# FE1_1S-SCH.net
KiCad netlist of a schematic drawn in Altium Designer
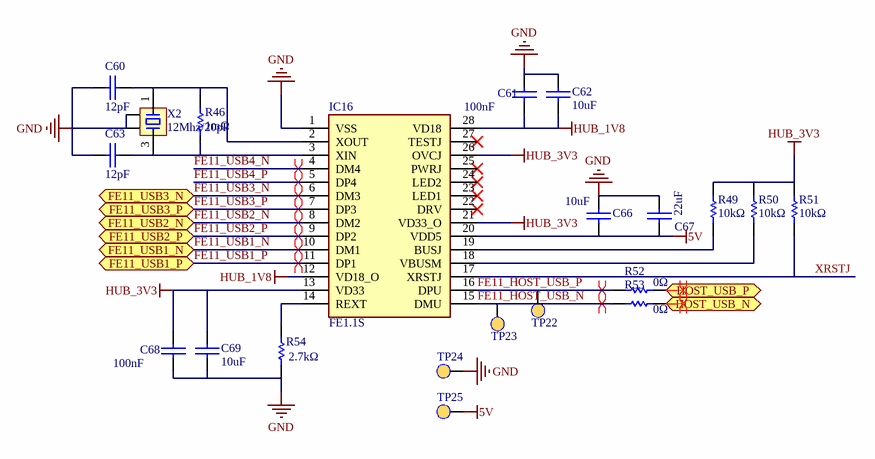
[diagram p0: FE1.1S-SCH.SchDoc]

(export (version "E")
  (design (tool "Eeschema 10.0.6"))
  (components
    (comp (ref "C60")
      (value "12pF")
      (footprint "C_0402")
      (description "贴片电容")
      (fields (field (name "MANUFACTURER_PART_NUMBER") "±5% /25V"))
      (libsource (lib "IntLib-Passive") (part "Cap_Chip"))
    )
    (comp (ref "C61")
      (value "100nF")
      (footprint "C_0402")
      (description "贴片电容")
      (fields (field (name "MANUFACTURER_PART_NUMBER") "±10% /25V"))
      (libsource (lib "IntLib-Passive") (part "Cap_Chip"))
    )
    (comp (ref "C62")
      (value "10uF")
      (footprint "C_0603")
      (description "贴片电容")
      (fields (field (name "MANUFACTURER_PART_NUMBER") "±10% /25V"))
      (libsource (lib "IntLib-Passive") (part "Cap_Chip"))
    )
    (comp (ref "C63")
      (value "12pF")
      (footprint "C_0402")
      (description "贴片电容")
      (fields (field (name "MANUFACTURER_PART_NUMBER") "±5% /25V"))
      (libsource (lib "IntLib-Passive") (part "Cap_Chip"))
    )
    (comp (ref "C66")
      (value "10uF")
      (footprint "C_0603")
      (description "贴片电容")
      (fields (field (name "MANUFACTURER_PART_NUMBER") "±10% /25V"))
      (libsource (lib "IntLib-Passive") (part "Cap_Chip"))
    )
    (comp (ref "C67")
      (value "22uF")
      (footprint "C_0805")
      (description "贴片电容")
      (fields (field (name "MANUFACTURER_PART_NUMBER") "±10% /25V"))
      (libsource (lib "IntLib-Passive") (part "Cap_Chip"))
    )
    (comp (ref "C68")
      (value "100nF")
      (footprint "C_0402")
      (description "贴片电容")
      (fields (field (name "MANUFACTURER_PART_NUMBER") "±10% /25V"))
      (libsource (lib "IntLib-Passive") (part "Cap_Chip"))
    )
    (comp (ref "C69")
      (value "10uF")
      (footprint "C_0603")
      (description "贴片电容")
      (fields (field (name "MANUFACTURER_PART_NUMBER") "±10% /25V"))
      (libsource (lib "IntLib-Passive") (part "Cap_Chip"))
    )
    (comp (ref "IC16")
      (value "FE1.1S")
      (footprint "SSOP-28N-150MIL")
      (description "USB2.0 Hub 4口芯片")
      (fields (field (name "MANUFACTURER_PART_NUMBER") "FE1.1S-BSOP28BCN"))
      (libsource (lib "IntLib-IC") (part "FE1.1S"))
    )
    (comp (ref "R46")
      (value "1mΩ")
      (footprint "R_0402")
      (description "贴片电阻")
      (fields (field (name "MANUFACTURER_PART_NUMBER") "±1%"))
      (libsource (lib "IntLib-Passive") (part "Res_Chip"))
    )
    (comp (ref "R49")
      (value "10kΩ")
      (footprint "R_0402")
      (description "贴片电阻")
      (fields (field (name "MANUFACTURER_PART_NUMBER") "±1%"))
      (libsource (lib "IntLib-Passive") (part "Res_Chip"))
    )
    (comp (ref "R50")
      (value "10kΩ")
      (footprint "R_0402")
      (description "贴片电阻")
      (fields (field (name "MANUFACTURER_PART_NUMBER") "±1%"))
      (libsource (lib "IntLib-Passive") (part "Res_Chip"))
    )
    (comp (ref "R51")
      (value "10kΩ")
      (footprint "R_0402")
      (description "贴片电阻")
      (fields (field (name "MANUFACTURER_PART_NUMBER") "±1%"))
      (libsource (lib "IntLib-Passive") (part "Res_Chip"))
    )
    (comp (ref "R52")
      (value "0Ω")
      (footprint "R_0603")
      (description "贴片电阻")
      (fields (field (name "MANUFACTURER_PART_NUMBER") "±1%"))
      (libsource (lib "IntLib-Passive") (part "Res_Chip"))
    )
    (comp (ref "R53")
      (value "0Ω")
      (footprint "R_0603")
      (description "贴片电阻")
      (fields (field (name "MANUFACTURER_PART_NUMBER") "±1%"))
      (libsource (lib "IntLib-Passive") (part "Res_Chip"))
    )
    (comp (ref "R54")
      (value "2.7kΩ")
      (footprint "R_0402")
      (description "贴片电阻")
      (fields (field (name "MANUFACTURER_PART_NUMBER") "±1%"))
      (libsource (lib "IntLib-Passive") (part "Res_Chip"))
    )
    (comp (ref "TP22")
      (value "TP")
      (footprint "TP1.4mm")
      (description "测试点")
      (libsource (lib "MiscParts") (part "TP"))
    )
    (comp (ref "TP23")
      (value "TP")
      (footprint "TP1.4mm")
      (description "测试点")
      (libsource (lib "MiscParts") (part "TP"))
    )
    (comp (ref "TP24")
      (value "TP")
      (footprint "TP1.4mm")
      (description "测试点")
      (libsource (lib "MiscParts") (part "TP"))
    )
    (comp (ref "TP25")
      (value "TP")
      (footprint "TP1.4mm")
      (description "测试点")
      (libsource (lib "MiscParts") (part "TP"))
    )
    (comp (ref "X2")
      (value "12Mhz/20pF")
      (footprint "XTAL_3225-4P")
      (description "4脚无源晶振")
      (libsource (lib "IntLib-Active") (part "Crystal_4P"))
    )
  )
  (nets
    (net (code "1") (name "/FE11_HOST_USB_N") (class "Default")
      (node (ref "IC16") (pin "15") (pinfunction "DMU_15") (pintype "passive"))
      (node (ref "R53") (pin "2") (pinfunction "2_2") (pintype "passive"))
      (node (ref "TP23") (pin "1") (pinfunction "TP_1") (pintype "passive"))
    )
    (net (code "2") (name "/FE11_HOST_USB_P") (class "Default")
      (node (ref "IC16") (pin "16") (pinfunction "DPU_16") (pintype "passive"))
      (node (ref "R52") (pin "2") (pinfunction "2_2") (pintype "passive"))
      (node (ref "TP22") (pin "1") (pinfunction "TP_1") (pintype "passive"))
    )
    (net (code "3") (name "/FE11_USB1_N") (class "Default")
      (node (ref "IC16") (pin "10") (pinfunction "DM1_10") (pintype "passive"))
    )
    (net (code "4") (name "/FE11_USB1_P") (class "Default")
      (node (ref "IC16") (pin "11") (pinfunction "DP1_11") (pintype "passive"))
    )
    (net (code "5") (name "/FE11_USB2_N") (class "Default")
      (node (ref "IC16") (pin "8") (pinfunction "DM2_8") (pintype "passive"))
    )
    (net (code "6") (name "/FE11_USB2_P") (class "Default")
      (node (ref "IC16") (pin "9") (pinfunction "DP2_9") (pintype "passive"))
    )
    (net (code "7") (name "/FE11_USB3_N") (class "Default")
      (node (ref "IC16") (pin "6") (pinfunction "DM3_6") (pintype "passive"))
    )
    (net (code "8") (name "/FE11_USB3_P") (class "Default")
      (node (ref "IC16") (pin "7") (pinfunction "DP3_7") (pintype "passive"))
    )
    (net (code "9") (name "/FE11_USB4_N") (class "Default")
      (node (ref "IC16") (pin "4") (pinfunction "DM4_4") (pintype "passive"))
    )
    (net (code "10") (name "/FE11_USB4_P") (class "Default")
      (node (ref "IC16") (pin "5") (pinfunction "DP4_5") (pintype "passive"))
    )
    (net (code "11") (name "/HOST_USB_N") (class "Default")
      (node (ref "R53") (pin "1") (pinfunction "1_1") (pintype "passive"))
    )
    (net (code "12") (name "/HOST_USB_P") (class "Default")
      (node (ref "R52") (pin "1") (pinfunction "1_1") (pintype "passive"))
    )
    (net (code "13") (name "/XRSTJ") (class "Default")
      (node (ref "IC16") (pin "17") (pinfunction "XRSTJ_17") (pintype "passive"))
      (node (ref "R51") (pin "1") (pinfunction "1_1") (pintype "passive"))
    )
    (net (code "14") (name "5V") (class "Default")
      (node (ref "C66") (pin "2") (pinfunction "2_2") (pintype "passive"))
      (node (ref "C67") (pin "1") (pinfunction "1_1") (pintype "passive"))
      (node (ref "IC16") (pin "20") (pinfunction "VDD5_20") (pintype "passive"))
      (node (ref "TP25") (pin "1") (pinfunction "TP_1") (pintype "passive"))
    )
    (net (code "15") (name "GND") (class "Default")
      (node (ref "C60") (pin "2") (pinfunction "2_2") (pintype "passive"))
      (node (ref "C61") (pin "2") (pinfunction "2_2") (pintype "passive"))
      (node (ref "C62") (pin "1") (pinfunction "1_1") (pintype "passive"))
      (node (ref "C63") (pin "1") (pinfunction "1_1") (pintype "passive"))
      (node (ref "C66") (pin "1") (pinfunction "1_1") (pintype "passive"))
      (node (ref "C67") (pin "2") (pinfunction "2_2") (pintype "passive"))
      (node (ref "C68") (pin "1") (pinfunction "1_1") (pintype "passive"))
      (node (ref "C69") (pin "2") (pinfunction "2_2") (pintype "passive"))
      (node (ref "IC16") (pin "1") (pinfunction "VSS_1") (pintype "passive"))
      (node (ref "R54") (pin "1") (pinfunction "1_1") (pintype "passive"))
      (node (ref "TP24") (pin "1") (pinfunction "TP_1") (pintype "passive"))
      (node (ref "X2") (pin "2") (pinfunction "2_2") (pintype "passive"))
      (node (ref "X2") (pin "4") (pinfunction "4_4") (pintype "passive"))
    )
    (net (code "16") (name "HUB_1V8") (class "Default")
      (node (ref "C61") (pin "1") (pinfunction "1_1") (pintype "passive"))
      (node (ref "C62") (pin "2") (pinfunction "2_2") (pintype "passive"))
      (node (ref "IC16") (pin "12") (pinfunction "VD18_O_12") (pintype "passive"))
      (node (ref "IC16") (pin "28") (pinfunction "VD18_28") (pintype "passive"))
    )
    (net (code "17") (name "HUB_3V3") (class "Default")
      (node (ref "C68") (pin "2") (pinfunction "2_2") (pintype "passive"))
      (node (ref "C69") (pin "1") (pinfunction "1_1") (pintype "passive"))
      (node (ref "IC16") (pin "13") (pinfunction "VD33_13") (pintype "passive"))
      (node (ref "IC16") (pin "21") (pinfunction "VD33_O_21") (pintype "passive"))
      (node (ref "IC16") (pin "26") (pinfunction "OVCJ_26") (pintype "passive"))
      (node (ref "R49") (pin "2") (pinfunction "2_2") (pintype "passive"))
      (node (ref "R50") (pin "2") (pinfunction "2_2") (pintype "passive"))
      (node (ref "R51") (pin "2") (pinfunction "2_2") (pintype "passive"))
    )
    (net (code "18") (name "Net-(IC16-BUSJ)") (class "Default")
      (node (ref "IC16") (pin "19") (pinfunction "BUSJ_19") (pintype "passive"))
      (node (ref "R49") (pin "1") (pinfunction "1_1") (pintype "passive"))
    )
    (net (code "19") (name "Net-(IC16-REXT)") (class "Default")
      (node (ref "IC16") (pin "14") (pinfunction "REXT_14") (pintype "passive"))
      (node (ref "R54") (pin "2") (pinfunction "2_2") (pintype "passive"))
    )
    (net (code "20") (name "Net-(IC16-VBUSM)") (class "Default")
      (node (ref "IC16") (pin "18") (pinfunction "VBUSM_18") (pintype "passive"))
      (node (ref "R50") (pin "1") (pinfunction "1_1") (pintype "passive"))
    )
    (net (code "21") (name "Net-(IC16-XIN)") (class "Default")
      (node (ref "C63") (pin "2") (pinfunction "2_2") (pintype "passive"))
      (node (ref "IC16") (pin "3") (pinfunction "XIN_3") (pintype "passive"))
      (node (ref "R46") (pin "1") (pinfunction "1_1") (pintype "passive"))
      (node (ref "X2") (pin "3") (pinfunction "3_3") (pintype "passive"))
    )
    (net (code "22") (name "Net-(IC16-XOUT)") (class "Default")
      (node (ref "C60") (pin "1") (pinfunction "1_1") (pintype "passive"))
      (node (ref "IC16") (pin "2") (pinfunction "XOUT_2") (pintype "passive"))
      (node (ref "R46") (pin "2") (pinfunction "2_2") (pintype "passive"))
      (node (ref "X2") (pin "1") (pinfunction "1_1") (pintype "passive"))
    )
    (net (code "23") (name "unconnected-(IC16-DRV-Pad22)") (class "Default")
      (node (ref "IC16") (pin "22") (pinfunction "DRV_22") (pintype "passive+no_connect"))
    )
    (net (code "24") (name "unconnected-(IC16-LED1-Pad23)") (class "Default")
      (node (ref "IC16") (pin "23") (pinfunction "LED1_23") (pintype "passive+no_connect"))
    )
    (net (code "25") (name "unconnected-(IC16-LED2-Pad24)") (class "Default")
      (node (ref "IC16") (pin "24") (pinfunction "LED2_24") (pintype "passive+no_connect"))
    )
    (net (code "26") (name "unconnected-(IC16-PWRJ-Pad25)") (class "Default")
      (node (ref "IC16") (pin "25") (pinfunction "PWRJ_25") (pintype "passive+no_connect"))
    )
    (net (code "27") (name "unconnected-(IC16-TESTJ-Pad27)") (class "Default")
      (node (ref "IC16") (pin "27") (pinfunction "TESTJ_27") (pintype "passive+no_connect"))
    )
  )
)
